# Moteino.net
KiCad netlist of a schematic drawn in EAGLE
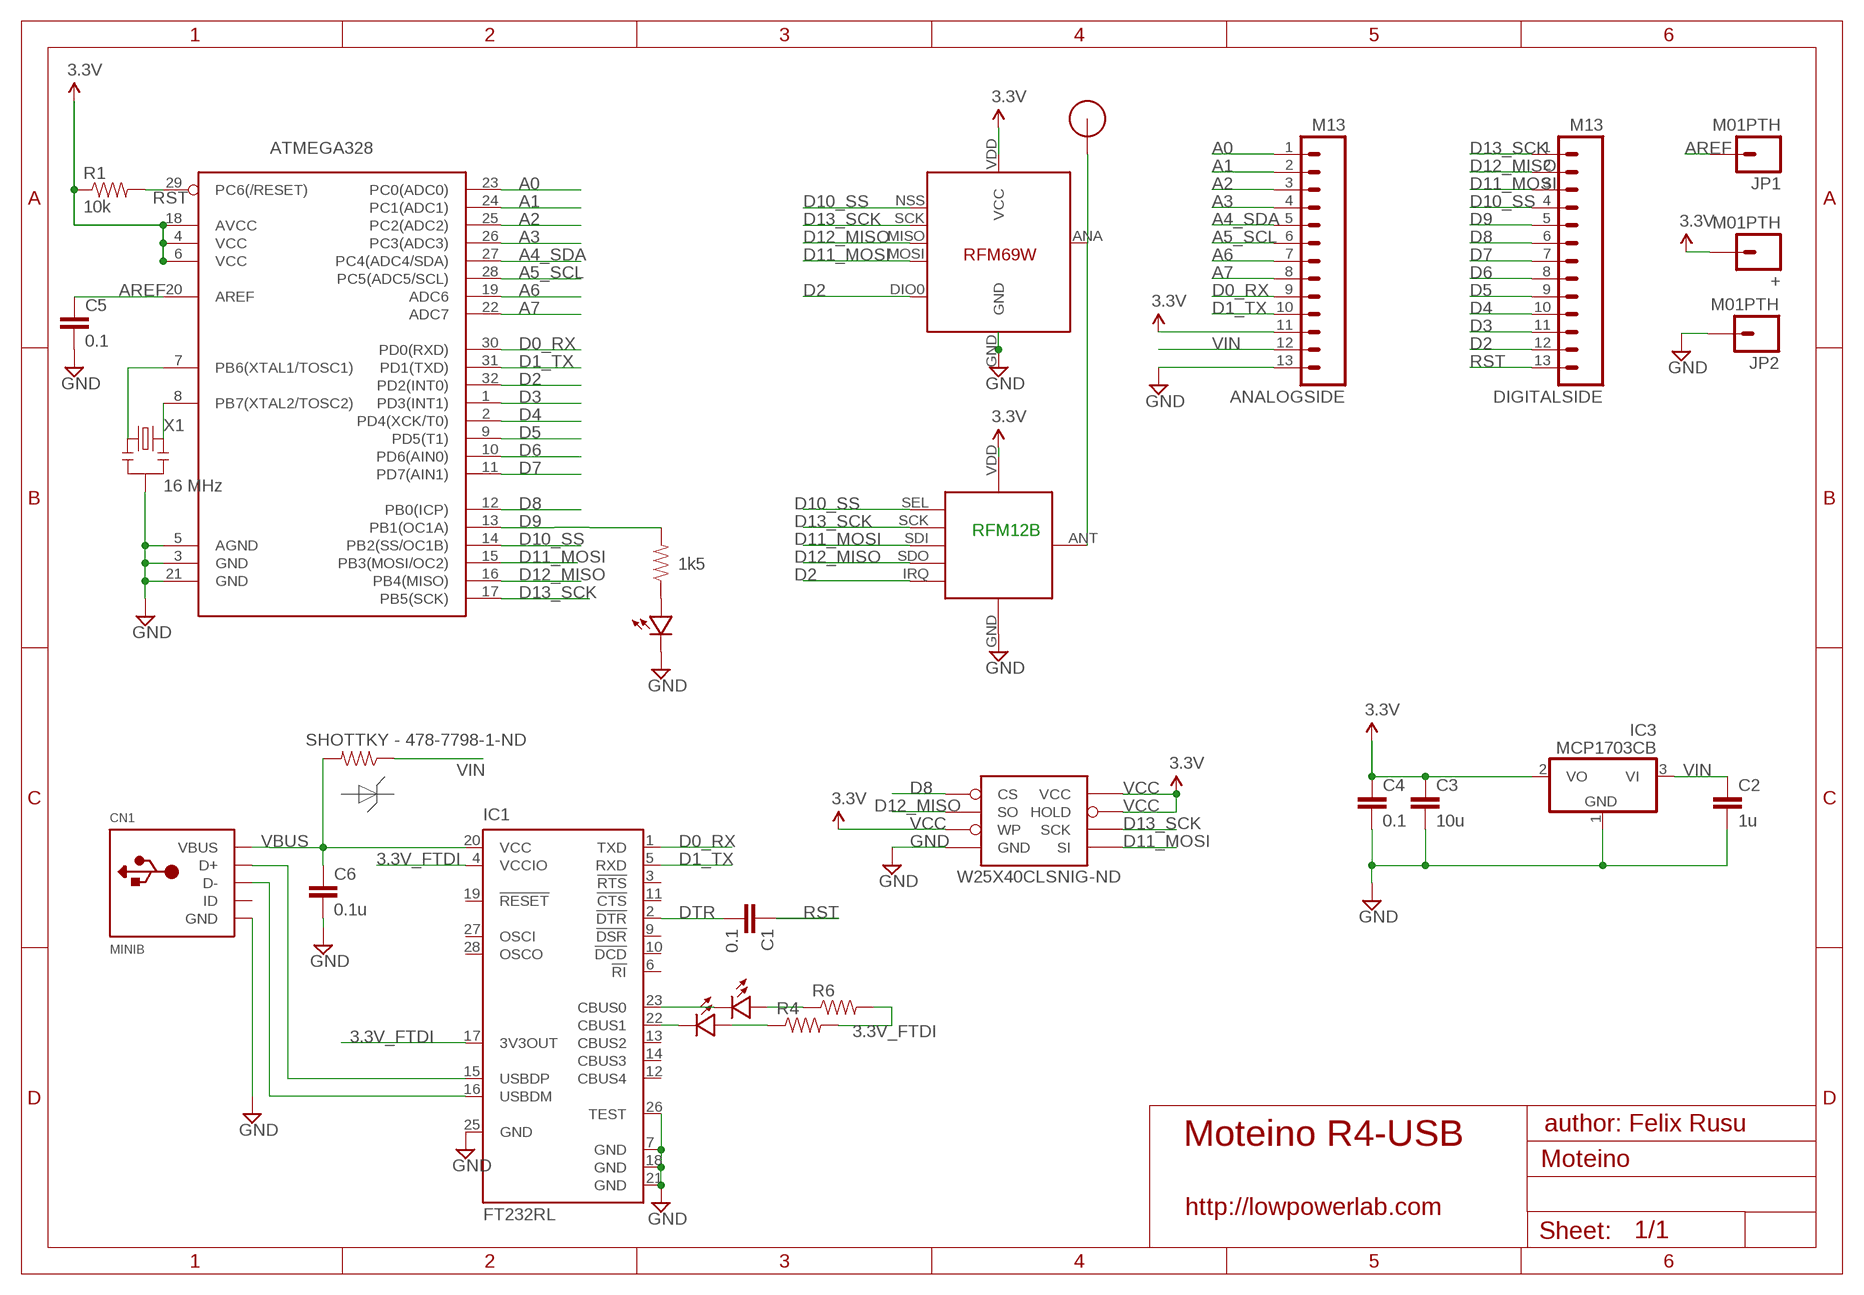
[diagram p0: schematic, sheet 1]

(export (version "E")
  (design (tool "Eeschema 10.0.6"))
  (components
    (comp (ref "+")
      (value "M01PTH")
      (footprint "eagle-import:1X01")
      (libsource (lib "eagle-import") (part "M01PTH"))
    )
    (comp (ref "ANALOGSIDE")
      (value "M13")
      (footprint "eagle-import:1X13")
      (libsource (lib "eagle-import") (part "M13"))
    )
    (comp (ref "ATMEGA328")
      (value "ATMega-328")
      (footprint "eagle-import:TQFP32-08")
      (libsource (lib "eagle-import") (part "ATMEGA168/328TQFP32"))
    )
    (comp (ref "C1")
      (value "0.1")
      (footprint "eagle-import:0603-CAP")
      (libsource (lib "eagle-import") (part "CAP0603-CAP"))
    )
    (comp (ref "C2")
      (value "1u")
      (footprint "eagle-import:0603-CAP")
      (libsource (lib "eagle-import") (part "CAP0603-CAP"))
    )
    (comp (ref "C3")
      (value "10u")
      (footprint "eagle-import:0805-CAP")
      (libsource (lib "eagle-import") (part "CAP0805-CAP"))
    )
    (comp (ref "C4")
      (value "0.1")
      (footprint "eagle-import:0603-CAP")
      (libsource (lib "eagle-import") (part "CAP0603-CAP"))
    )
    (comp (ref "C5")
      (value "0.1")
      (footprint "eagle-import:0603-CAP")
      (libsource (lib "eagle-import") (part "CAP0603-CAP"))
    )
    (comp (ref "C6")
      (value "0.1u")
      (footprint "eagle-import:0603-CAP")
      (libsource (lib "eagle-import") (part "CAP0603-CAP"))
    )
    (comp (ref "CN1")
      (value "MINIB")
      (footprint "eagle-import:USB-MINIB")
      (libsource (lib "eagle-import") (part "USBMINIB"))
    )
    (comp (ref "D")
      (value "SHOTTKY - 478-7798-1-ND")
      (footprint "eagle-import:0603-RES")
      (libsource (lib "eagle-import") (part "RESISTOR0603-RES"))
    )
    (comp (ref "DIGITALSIDE")
      (value "M13")
      (footprint "eagle-import:1X13")
      (libsource (lib "eagle-import") (part "M13"))
    )
    (comp (ref "IC1")
      (value "FT232RL")
      (footprint "eagle-import:SSOP28")
      (libsource (lib "eagle-import") (part "FT232RL"))
    )
    (comp (ref "IC3")
      (value "MCP1703CB")
      (footprint "eagle-import:SOT23")
      (libsource (lib "eagle-import") (part "MCP1703CB"))
    )
    (comp (ref "JP1")
      (value "M01PTH")
      (footprint "eagle-import:1X01")
      (libsource (lib "eagle-import") (part "M01PTH"))
    )
    (comp (ref "JP2")
      (value "M01PTH")
      (footprint "eagle-import:1X01")
      (libsource (lib "eagle-import") (part "M01PTH"))
    )
    (comp (ref "R1")
      (value "10k")
      (footprint "eagle-import:0603-RES")
      (libsource (lib "eagle-import") (part "RESISTOR0603-RES"))
    )
    (comp (ref "R2")
      (value "1k5")
      (footprint "eagle-import:0603-RES")
      (libsource (lib "eagle-import") (part "RESISTOR0603-RES"))
    )
    (comp (ref "R4")
      (value "RESISTOR0603-RES")
      (footprint "eagle-import:0603-RES")
      (libsource (lib "eagle-import") (part "RESISTOR0603-RES"))
    )
    (comp (ref "R6")
      (value "RESISTOR0603-RES")
      (footprint "eagle-import:0603-RES")
      (libsource (lib "eagle-import") (part "RESISTOR0603-RES"))
    )
    (comp (ref "RFM12B")
      (value "RFM12B_MINPADS")
      (footprint "eagle-import:RFM12B-MINPADS")
      (libsource (lib "eagle-import") (part "RFM12B_MINPADS"))
    )
    (comp (ref "U$1")
      (value "RFM12B_ANTENNA")
      (footprint "eagle-import:RFM12B-ANTENNA")
      (libsource (lib "eagle-import") (part "RFM12B_ANTENNA"))
    )
    (comp (ref "U$2")
      (value "LED0603")
      (footprint "eagle-import:0603-LED")
      (libsource (lib "eagle-import") (part "LED0603"))
    )
    (comp (ref "U$4")
      (value "LED0603")
      (footprint "eagle-import:0603-LED")
      (libsource (lib "eagle-import") (part "LED0603"))
    )
    (comp (ref "U$5")
      (value "RFM69")
      (footprint "eagle-import:RFM69W-MINPADS")
      (libsource (lib "eagle-import") (part "RFM69"))
    )
    (comp (ref "U$7")
      (value "LED0603")
      (footprint "eagle-import:0603-LED")
      (libsource (lib "eagle-import") (part "LED0603"))
    )
    (comp (ref "W25X40CLSNIG-ND")
      (value "AT25F512BWIDE_5.3MM")
      (footprint "eagle-import:SO08WIDE")
      (libsource (lib "eagle-import") (part "AT25F512BWIDE_5.3MM"))
    )
    (comp (ref "X1")
      (value "16 MHz")
      (footprint "eagle-import:RESONATOR-SMD")
      (libsource (lib "eagle-import") (part "RESONATORSMD"))
    )
  )
  (nets
    (net (code "1") (name "/3.3V_FTDI") (class "Default")
      (node (ref "IC1") (pin "17") (pinfunction "3V3OUT_17") (pintype "input"))
      (node (ref "IC1") (pin "4") (pinfunction "VCCIO_4") (pintype "input"))
      (node (ref "R4") (pin "2") (pinfunction "2_2") (pintype "passive"))
      (node (ref "R6") (pin "2") (pinfunction "2_2") (pintype "passive"))
    )
    (net (code "2") (name "/A0") (class "Default")
      (node (ref "ANALOGSIDE") (pin "1") (pinfunction "1_1") (pintype "passive"))
      (node (ref "ATMEGA328") (pin "23") (pinfunction "PC0(ADC0)_23") (pintype "bidirectional"))
    )
    (net (code "3") (name "/A1") (class "Default")
      (node (ref "ANALOGSIDE") (pin "2") (pinfunction "2_2") (pintype "passive"))
      (node (ref "ATMEGA328") (pin "24") (pinfunction "PC1(ADC1)_24") (pintype "bidirectional"))
    )
    (net (code "4") (name "/A2") (class "Default")
      (node (ref "ANALOGSIDE") (pin "3") (pinfunction "3_3") (pintype "passive"))
      (node (ref "ATMEGA328") (pin "25") (pinfunction "PC2(ADC2)_25") (pintype "bidirectional"))
    )
    (net (code "5") (name "/A3") (class "Default")
      (node (ref "ANALOGSIDE") (pin "4") (pinfunction "4_4") (pintype "passive"))
      (node (ref "ATMEGA328") (pin "26") (pinfunction "PC3(ADC3)_26") (pintype "bidirectional"))
    )
    (net (code "6") (name "/A4_SDA") (class "Default")
      (node (ref "ANALOGSIDE") (pin "5") (pinfunction "5_5") (pintype "passive"))
      (node (ref "ATMEGA328") (pin "27") (pinfunction "PC4(ADC4/SDA)_27") (pintype "bidirectional"))
    )
    (net (code "7") (name "/A5_SCL") (class "Default")
      (node (ref "ANALOGSIDE") (pin "6") (pinfunction "6_6") (pintype "passive"))
      (node (ref "ATMEGA328") (pin "28") (pinfunction "PC5(ADC5/SCL)_28") (pintype "bidirectional"))
    )
    (net (code "8") (name "/A6") (class "Default")
      (node (ref "ANALOGSIDE") (pin "7") (pinfunction "7_7") (pintype "passive"))
      (node (ref "ATMEGA328") (pin "19") (pinfunction "ADC6_19") (pintype "bidirectional"))
    )
    (net (code "9") (name "/A7") (class "Default")
      (node (ref "ANALOGSIDE") (pin "8") (pinfunction "8_8") (pintype "passive"))
      (node (ref "ATMEGA328") (pin "22") (pinfunction "ADC7_22") (pintype "bidirectional"))
    )
    (net (code "10") (name "/AREF") (class "Default")
      (node (ref "ATMEGA328") (pin "20") (pinfunction "AREF_20") (pintype "bidirectional"))
      (node (ref "C5") (pin "1") (pinfunction "1_1") (pintype "passive"))
      (node (ref "JP1") (pin "1") (pinfunction "1_1") (pintype "passive"))
    )
    (net (code "11") (name "/D0_RX") (class "Default")
      (node (ref "ANALOGSIDE") (pin "9") (pinfunction "9_9") (pintype "passive"))
      (node (ref "ATMEGA328") (pin "30") (pinfunction "PD0(RXD)_30") (pintype "bidirectional"))
      (node (ref "IC1") (pin "1") (pinfunction "TXD_1") (pintype "input"))
    )
    (net (code "12") (name "/D1_TX") (class "Default")
      (node (ref "ANALOGSIDE") (pin "10") (pinfunction "10_10") (pintype "passive"))
      (node (ref "ATMEGA328") (pin "31") (pinfunction "PD1(TXD)_31") (pintype "bidirectional"))
      (node (ref "IC1") (pin "5") (pinfunction "RXD_5") (pintype "input"))
    )
    (net (code "13") (name "/D2") (class "Default")
      (node (ref "ATMEGA328") (pin "32") (pinfunction "PD2(INT0)_32") (pintype "bidirectional"))
      (node (ref "DIGITALSIDE") (pin "12") (pinfunction "12_12") (pintype "passive"))
      (node (ref "RFM12B") (pin "IRQ") (pinfunction "IRQ_IRQ") (pintype "bidirectional"))
      (node (ref "U$5") (pin "DIO0") (pinfunction "DIO0_DIO0") (pintype "open_collector"))
    )
    (net (code "14") (name "/D3") (class "Default")
      (node (ref "ATMEGA328") (pin "1") (pinfunction "PD3(INT1)_1") (pintype "bidirectional"))
      (node (ref "DIGITALSIDE") (pin "11") (pinfunction "11_11") (pintype "passive"))
    )
    (net (code "15") (name "/D4") (class "Default")
      (node (ref "ATMEGA328") (pin "2") (pinfunction "PD4(XCK/T0)_2") (pintype "bidirectional"))
      (node (ref "DIGITALSIDE") (pin "10") (pinfunction "10_10") (pintype "passive"))
    )
    (net (code "16") (name "/D5") (class "Default")
      (node (ref "ATMEGA328") (pin "9") (pinfunction "PD5(T1)_9") (pintype "bidirectional"))
      (node (ref "DIGITALSIDE") (pin "9") (pinfunction "9_9") (pintype "passive"))
    )
    (net (code "17") (name "/D6") (class "Default")
      (node (ref "ATMEGA328") (pin "10") (pinfunction "PD6(AIN0)_10") (pintype "bidirectional"))
      (node (ref "DIGITALSIDE") (pin "8") (pinfunction "8_8") (pintype "passive"))
    )
    (net (code "18") (name "/D7") (class "Default")
      (node (ref "ATMEGA328") (pin "11") (pinfunction "PD7(AIN1)_11") (pintype "bidirectional"))
      (node (ref "DIGITALSIDE") (pin "7") (pinfunction "7_7") (pintype "passive"))
    )
    (net (code "19") (name "/D8") (class "Default")
      (node (ref "ATMEGA328") (pin "12") (pinfunction "PB0(ICP)_12") (pintype "bidirectional"))
      (node (ref "DIGITALSIDE") (pin "6") (pinfunction "6_6") (pintype "passive"))
      (node (ref "W25X40CLSNIG-ND") (pin "1") (pinfunction "CS_1") (pintype "bidirectional"))
    )
    (net (code "20") (name "/D9") (class "Default")
      (node (ref "ATMEGA328") (pin "13") (pinfunction "PB1(OC1A)_13") (pintype "bidirectional"))
      (node (ref "DIGITALSIDE") (pin "5") (pinfunction "5_5") (pintype "passive"))
      (node (ref "R2") (pin "2") (pinfunction "2_2") (pintype "passive"))
    )
    (net (code "21") (name "/D10_SS") (class "Default")
      (node (ref "ATMEGA328") (pin "14") (pinfunction "PB2(SS/OC1B)_14") (pintype "bidirectional"))
      (node (ref "DIGITALSIDE") (pin "4") (pinfunction "4_4") (pintype "passive"))
      (node (ref "RFM12B") (pin "SEL") (pinfunction "SEL_SEL") (pintype "bidirectional"))
      (node (ref "U$5") (pin "NSS") (pinfunction "SEL_NSS") (pintype "input"))
    )
    (net (code "22") (name "/D11_MOSI") (class "Default")
      (node (ref "ATMEGA328") (pin "15") (pinfunction "PB3(MOSI/OC2)_15") (pintype "bidirectional"))
      (node (ref "DIGITALSIDE") (pin "3") (pinfunction "3_3") (pintype "passive"))
      (node (ref "RFM12B") (pin "SDI") (pinfunction "SDI/MOSI_SDI") (pintype "bidirectional"))
      (node (ref "U$5") (pin "MOSI") (pinfunction "MOSI_MOSI") (pintype "output"))
      (node (ref "W25X40CLSNIG-ND") (pin "5") (pinfunction "SI_5") (pintype "bidirectional"))
    )
    (net (code "23") (name "/D12_MISO") (class "Default")
      (node (ref "ATMEGA328") (pin "16") (pinfunction "PB4(MISO)_16") (pintype "bidirectional"))
      (node (ref "DIGITALSIDE") (pin "2") (pinfunction "2_2") (pintype "passive"))
      (node (ref "RFM12B") (pin "SDO") (pinfunction "SDO/MISO_SDO") (pintype "bidirectional"))
      (node (ref "U$5") (pin "MISO") (pinfunction "MISO_MISO") (pintype "input"))
      (node (ref "W25X40CLSNIG-ND") (pin "2") (pinfunction "SO_2") (pintype "bidirectional"))
    )
    (net (code "24") (name "/D13_SCK") (class "Default")
      (node (ref "ATMEGA328") (pin "17") (pinfunction "PB5(SCK)_17") (pintype "bidirectional"))
      (node (ref "DIGITALSIDE") (pin "1") (pinfunction "1_1") (pintype "passive"))
      (node (ref "RFM12B") (pin "SCK") (pinfunction "SCK_SCK") (pintype "bidirectional"))
      (node (ref "U$5") (pin "SCK") (pinfunction "SCK_SCK") (pintype "input"))
      (node (ref "W25X40CLSNIG-ND") (pin "6") (pinfunction "SCK_6") (pintype "bidirectional"))
    )
    (net (code "25") (name "/DTR") (class "Default")
      (node (ref "C1") (pin "2") (pinfunction "2_2") (pintype "passive"))
      (node (ref "IC1") (pin "2") (pinfunction "~{DTR}_2") (pintype "input"))
    )
    (net (code "26") (name "/RST") (class "Default")
      (node (ref "ATMEGA328") (pin "29") (pinfunction "PC6(/RESET)_29") (pintype "bidirectional"))
      (node (ref "C1") (pin "1") (pinfunction "1_1") (pintype "passive"))
      (node (ref "DIGITALSIDE") (pin "13") (pinfunction "13_13") (pintype "passive"))
      (node (ref "R1") (pin "2") (pinfunction "2_2") (pintype "passive"))
    )
    (net (code "27") (name "/VBUS") (class "Default")
      (node (ref "C6") (pin "1") (pinfunction "1_1") (pintype "passive"))
      (node (ref "CN1") (pin "VBUS") (pinfunction "VBUS_VBUS") (pintype "power_in"))
      (node (ref "D") (pin "2") (pinfunction "2_2") (pintype "passive"))
      (node (ref "IC1") (pin "20") (pinfunction "VCC_20") (pintype "input"))
    )
    (net (code "28") (name "/VIN") (class "Default")
      (node (ref "ANALOGSIDE") (pin "12") (pinfunction "12_12") (pintype "passive"))
      (node (ref "C2") (pin "1") (pinfunction "1_1") (pintype "passive"))
      (node (ref "D") (pin "1") (pinfunction "1_1") (pintype "passive"))
      (node (ref "IC3") (pin "3") (pinfunction "VI_3") (pintype "input"))
    )
    (net (code "29") (name "3.3V") (class "Default")
      (node (ref "+") (pin "1") (pinfunction "1_1") (pintype "passive"))
      (node (ref "ANALOGSIDE") (pin "11") (pinfunction "11_11") (pintype "passive"))
      (node (ref "ATMEGA328") (pin "18") (pinfunction "AVCC_18") (pintype "bidirectional"))
      (node (ref "ATMEGA328") (pin "4") (pinfunction "VCC_4") (pintype "bidirectional"))
      (node (ref "ATMEGA328") (pin "6") (pinfunction "VCC_6") (pintype "bidirectional"))
      (node (ref "C3") (pin "1") (pinfunction "1_1") (pintype "passive"))
      (node (ref "C4") (pin "1") (pinfunction "1_1") (pintype "passive"))
      (node (ref "IC3") (pin "2") (pinfunction "VO_2") (pintype "passive"))
      (node (ref "R1") (pin "1") (pinfunction "1_1") (pintype "passive"))
      (node (ref "RFM12B") (pin "VDD") (pinfunction "VDD_VDD") (pintype "bidirectional"))
      (node (ref "U$5") (pin "VDD") (pinfunction "VCC_VDD") (pintype "power_in"))
      (node (ref "W25X40CLSNIG-ND") (pin "3") (pinfunction "WP_3") (pintype "bidirectional"))
      (node (ref "W25X40CLSNIG-ND") (pin "7") (pinfunction "HOLD_7") (pintype "bidirectional"))
      (node (ref "W25X40CLSNIG-ND") (pin "8") (pinfunction "VCC_8") (pintype "bidirectional"))
    )
    (net (code "30") (name "GND") (class "Default")
      (node (ref "ANALOGSIDE") (pin "13") (pinfunction "13_13") (pintype "passive"))
      (node (ref "ATMEGA328") (pin "21") (pinfunction "GND_21") (pintype "bidirectional"))
      (node (ref "ATMEGA328") (pin "3") (pinfunction "GND_3") (pintype "bidirectional"))
      (node (ref "ATMEGA328") (pin "5") (pinfunction "AGND_5") (pintype "bidirectional"))
      (node (ref "C2") (pin "2") (pinfunction "2_2") (pintype "passive"))
      (node (ref "C3") (pin "2") (pinfunction "2_2") (pintype "passive"))
      (node (ref "C4") (pin "2") (pinfunction "2_2") (pintype "passive"))
      (node (ref "C5") (pin "2") (pinfunction "2_2") (pintype "passive"))
      (node (ref "C6") (pin "2") (pinfunction "2_2") (pintype "passive"))
      (node (ref "CN1") (pin "GND") (pinfunction "GND_GND") (pintype "power_in"))
      (node (ref "IC1") (pin "18") (pinfunction "GND_18") (pintype "input"))
      (node (ref "IC1") (pin "21") (pinfunction "GND_21") (pintype "input"))
      (node (ref "IC1") (pin "25") (pinfunction "GND_25") (pintype "input"))
      (node (ref "IC1") (pin "26") (pinfunction "TEST_26") (pintype "input"))
      (node (ref "IC1") (pin "7") (pinfunction "GND_7") (pintype "input"))
      (node (ref "IC3") (pin "1") (pinfunction "GND_1") (pintype "passive"))
      (node (ref "JP2") (pin "1") (pinfunction "1_1") (pintype "passive"))
      (node (ref "RFM12B") (pin "GND") (pinfunction "GND_GND") (pintype "bidirectional"))
      (node (ref "U$2") (pin "MINUS") (pinfunction "MINUS_MINUS") (pintype "passive"))
      (node (ref "U$5") (pin "GND") (pinfunction "GND_GND") (pintype "power_in"))
      (node (ref "W25X40CLSNIG-ND") (pin "4") (pinfunction "GND_4") (pintype "bidirectional"))
      (node (ref "X1") (pin "2") (pinfunction "2_2") (pintype "passive"))
    )
    (net (code "31") (name "Net-(ATMEGA328-PB6(XTAL1{slash}TOSC1))") (class "Default")
      (node (ref "ATMEGA328") (pin "7") (pinfunction "PB6(XTAL1/TOSC1)_7") (pintype "bidirectional"))
      (node (ref "X1") (pin "1") (pinfunction "1_1") (pintype "passive"))
    )
    (net (code "32") (name "Net-(ATMEGA328-PB7(XTAL2{slash}TOSC2))") (class "Default")
      (node (ref "ATMEGA328") (pin "8") (pinfunction "PB7(XTAL2/TOSC2)_8") (pintype "bidirectional"))
      (node (ref "X1") (pin "3") (pinfunction "3_3") (pintype "passive"))
    )
    (net (code "33") (name "Net-(IC1-CBUS0)") (class "Default")
      (node (ref "IC1") (pin "23") (pinfunction "CBUS0_23") (pintype "input"))
      (node (ref "U$4") (pin "MINUS") (pinfunction "MINUS_MINUS") (pintype "passive"))
    )
    (net (code "34") (name "Net-(IC1-CBUS1)") (class "Default")
      (node (ref "IC1") (pin "22") (pinfunction "CBUS1_22") (pintype "input"))
      (node (ref "U$7") (pin "MINUS") (pinfunction "MINUS_MINUS") (pintype "passive"))
    )
    (net (code "35") (name "Net-(IC1-USBDM)") (class "Default")
      (node (ref "CN1") (pin "D-") (pinfunction "D-_D-") (pintype "bidirectional"))
      (node (ref "IC1") (pin "16") (pinfunction "USBDM_16") (pintype "input"))
    )
    (net (code "36") (name "Net-(IC1-USBDP)") (class "Default")
      (node (ref "CN1") (pin "D+") (pinfunction "D+_D+") (pintype "bidirectional"))
      (node (ref "IC1") (pin "15") (pinfunction "USBDP_15") (pintype "input"))
    )
    (net (code "37") (name "Net-(R2-Pad1)") (class "Default")
      (node (ref "R2") (pin "1") (pinfunction "1_1") (pintype "passive"))
      (node (ref "U$2") (pin "PLUS") (pinfunction "PLUS_PLUS") (pintype "passive"))
    )
    (net (code "38") (name "Net-(R4-Pad1)") (class "Default")
      (node (ref "R4") (pin "1") (pinfunction "1_1") (pintype "passive"))
      (node (ref "U$7") (pin "PLUS") (pinfunction "PLUS_PLUS") (pintype "passive"))
    )
    (net (code "39") (name "Net-(R6-Pad1)") (class "Default")
      (node (ref "R6") (pin "1") (pinfunction "1_1") (pintype "passive"))
      (node (ref "U$4") (pin "PLUS") (pinfunction "PLUS_PLUS") (pintype "passive"))
    )
    (net (code "40") (name "Net-(U$1-1)") (class "Default")
      (node (ref "RFM12B") (pin "ANT") (pinfunction "ANT_ANT") (pintype "bidirectional"))
      (node (ref "U$1") (pin "P$1") (pinfunction "1_P$1") (pintype "bidirectional"))
      (node (ref "U$5") (pin "ANA") (pinfunction "ANT_ANA") (pintype "passive"))
    )
    (net (code "41") (name "unconnected-(CN1-PadID)") (class "Default")
      (node (ref "CN1") (pin "ID") (pinfunction "ID_ID") (pintype "bidirectional"))
    )
    (net (code "42") (name "unconnected-(IC1-CBUS2-Pad13)") (class "Default")
      (node (ref "IC1") (pin "13") (pinfunction "CBUS2_13") (pintype "input"))
    )
    (net (code "43") (name "unconnected-(IC1-CBUS3-Pad14)") (class "Default")
      (node (ref "IC1") (pin "14") (pinfunction "CBUS3_14") (pintype "input"))
    )
    (net (code "44") (name "unconnected-(IC1-CBUS4-Pad12)") (class "Default")
      (node (ref "IC1") (pin "12") (pinfunction "CBUS4_12") (pintype "input"))
    )
    (net (code "45") (name "unconnected-(IC1-OSCI-Pad27)") (class "Default")
      (node (ref "IC1") (pin "27") (pinfunction "OSCI_27") (pintype "input"))
    )
    (net (code "46") (name "unconnected-(IC1-OSCO-Pad28)") (class "Default")
      (node (ref "IC1") (pin "28") (pinfunction "OSCO_28") (pintype "input"))
    )
    (net (code "47") (name "unconnected-(IC1-~{CTS}-Pad11)") (class "Default")
      (node (ref "IC1") (pin "11") (pinfunction "~{CTS}_11") (pintype "input"))
    )
    (net (code "48") (name "unconnected-(IC1-~{DCD}-Pad10)") (class "Default")
      (node (ref "IC1") (pin "10") (pinfunction "~{DCD}_10") (pintype "input"))
    )
    (net (code "49") (name "unconnected-(IC1-~{DSR}-Pad9)") (class "Default")
      (node (ref "IC1") (pin "9") (pinfunction "~{DSR}_9") (pintype "input"))
    )
    (net (code "50") (name "unconnected-(IC1-~{RESET}-Pad19)") (class "Default")
      (node (ref "IC1") (pin "19") (pinfunction "~{RESET}_19") (pintype "input"))
    )
    (net (code "51") (name "unconnected-(IC1-~{RI}-Pad6)") (class "Default")
      (node (ref "IC1") (pin "6") (pinfunction "~{RI}_6") (pintype "input"))
    )
    (net (code "52") (name "unconnected-(IC1-~{RTS}-Pad3)") (class "Default")
      (node (ref "IC1") (pin "3") (pinfunction "~{RTS}_3") (pintype "input"))
    )
  )
)
